# GatewayVote_V2_0.net
KiCad netlist of a schematic drawn in EAGLE
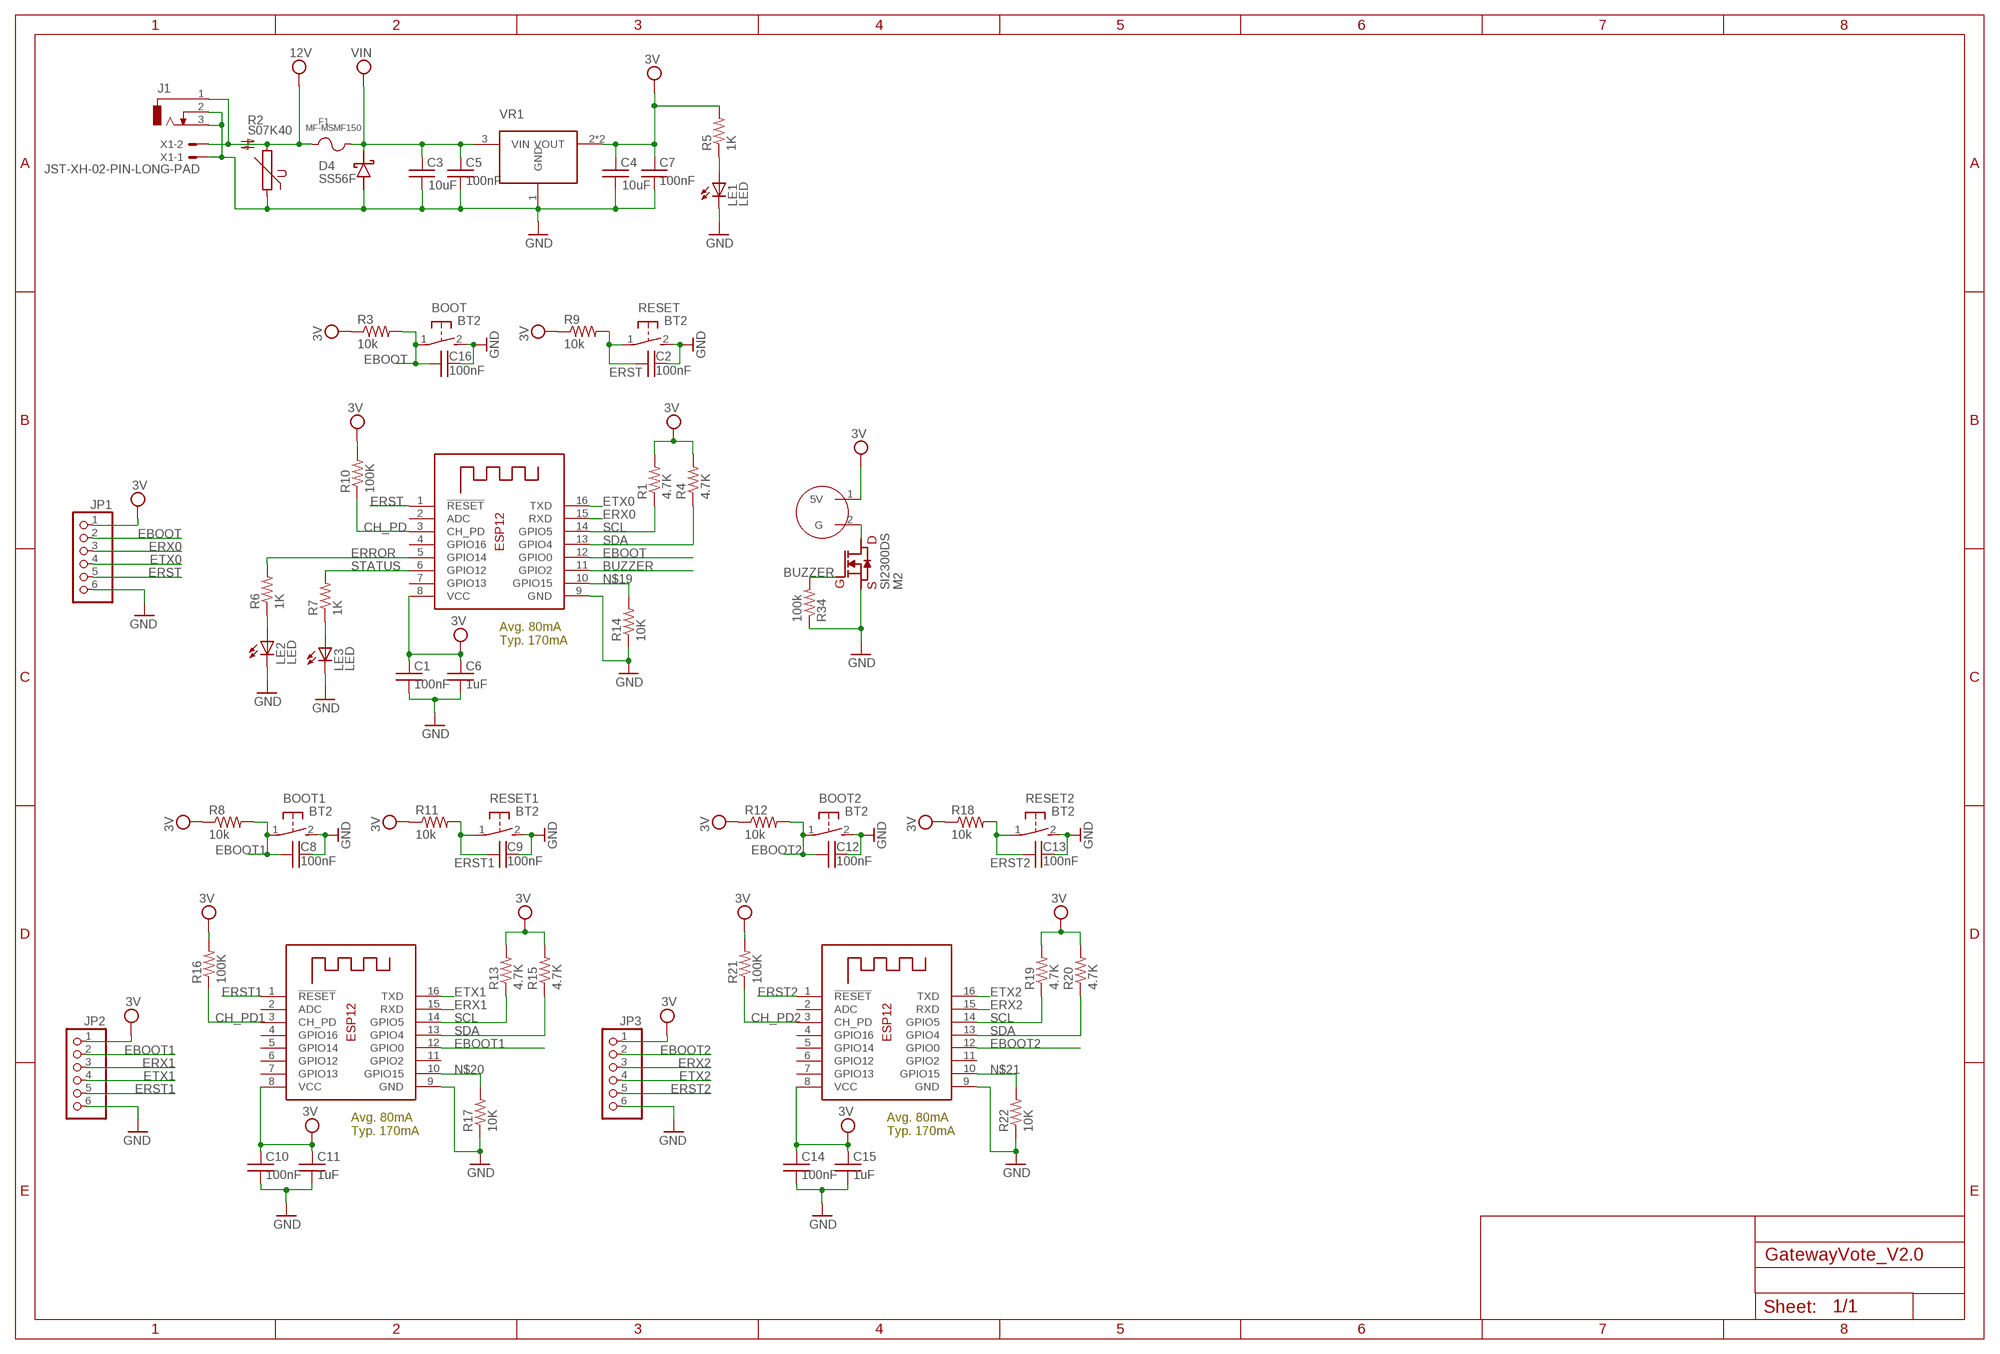
[diagram p0: schematic, sheet 1]

(export (version "E")
  (design (tool "Eeschema 10.0.6"))
  (components
    (comp (ref "BOOT")
      (value "BT2")
      (footprint "eagle-import:BT2")
      (libsource (lib "eagle-import") (part "BT2"))
    )
    (comp (ref "BOOT1")
      (value "BT2")
      (footprint "eagle-import:BT2")
      (libsource (lib "eagle-import") (part "BT2"))
    )
    (comp (ref "BOOT2")
      (value "BT2")
      (footprint "eagle-import:BT2")
      (libsource (lib "eagle-import") (part "BT2"))
    )
    (comp (ref "C1")
      (value "100nF")
      (footprint "eagle-import:0603")
      (libsource (lib "eagle-import") (part "C0603"))
    )
    (comp (ref "C2")
      (value "100nF")
      (footprint "eagle-import:0603")
      (libsource (lib "eagle-import") (part "Dkoi_C0603"))
    )
    (comp (ref "C3")
      (value "10uF")
      (footprint "eagle-import:0603")
      (libsource (lib "eagle-import") (part "Dkoi-updated_C0603"))
    )
    (comp (ref "C4")
      (value "10uF")
      (footprint "eagle-import:0603")
      (libsource (lib "eagle-import") (part "Dkoi-updated_C0603"))
    )
    (comp (ref "C5")
      (value "100nF")
      (footprint "eagle-import:0603")
      (libsource (lib "eagle-import") (part "Dkoi-updated_C0603"))
    )
    (comp (ref "C6")
      (value "1uF")
      (footprint "eagle-import:0603")
      (libsource (lib "eagle-import") (part "C0603"))
    )
    (comp (ref "C7")
      (value "100nF")
      (footprint "eagle-import:0603")
      (libsource (lib "eagle-import") (part "Dkoi-updated_C0603"))
    )
    (comp (ref "C8")
      (value "100nF")
      (footprint "eagle-import:0603")
      (libsource (lib "eagle-import") (part "Dkoi_C0603"))
    )
    (comp (ref "C9")
      (value "100nF")
      (footprint "eagle-import:0603")
      (libsource (lib "eagle-import") (part "Dkoi_C0603"))
    )
    (comp (ref "C10")
      (value "100nF")
      (footprint "eagle-import:0603")
      (libsource (lib "eagle-import") (part "C0603"))
    )
    (comp (ref "C11")
      (value "1uF")
      (footprint "eagle-import:0603")
      (libsource (lib "eagle-import") (part "C0603"))
    )
    (comp (ref "C12")
      (value "100nF")
      (footprint "eagle-import:0603")
      (libsource (lib "eagle-import") (part "Dkoi_C0603"))
    )
    (comp (ref "C13")
      (value "100nF")
      (footprint "eagle-import:0603")
      (libsource (lib "eagle-import") (part "Dkoi_C0603"))
    )
    (comp (ref "C14")
      (value "100nF")
      (footprint "eagle-import:0603")
      (libsource (lib "eagle-import") (part "C0603"))
    )
    (comp (ref "C15")
      (value "1uF")
      (footprint "eagle-import:0603")
      (libsource (lib "eagle-import") (part "C0603"))
    )
    (comp (ref "C16")
      (value "100nF")
      (footprint "eagle-import:0603")
      (libsource (lib "eagle-import") (part "Dkoi_C0603"))
    )
    (comp (ref "D4")
      (value "SS56F")
      (footprint "eagle-import:SMB")
      (libsource (lib "eagle-import") (part "SS56F"))
    )
    (comp (ref "F1")
      (value "MF-MSMF150")
      (footprint "eagle-import:FUSER_MF-MSMF150")
      (fields (field (name "MF") "Bourns"))
      (libsource (lib "eagle-import") (part "MF-MSMF150"))
    )
    (comp (ref "J1")
      (value "DCJ0303")
      (footprint "eagle-import:DCJ0303")
      (libsource (lib "eagle-import") (part "DCJ0303"))
    )
    (comp (ref "JP1")
      (value "PINHD-1X6")
      (footprint "eagle-import:1X06")
      (libsource (lib "eagle-import") (part "PINHD-1X6"))
    )
    (comp (ref "JP2")
      (value "PINHD-1X6")
      (footprint "eagle-import:1X06")
      (libsource (lib "eagle-import") (part "PINHD-1X6"))
    )
    (comp (ref "JP3")
      (value "PINHD-1X6")
      (footprint "eagle-import:1X06")
      (libsource (lib "eagle-import") (part "PINHD-1X6"))
    )
    (comp (ref "LE1")
      (value "LED")
      (footprint "eagle-import:LED3MM")
      (libsource (lib "eagle-import") (part "LED"))
    )
    (comp (ref "LE2")
      (value "LED")
      (footprint "eagle-import:LED3MM")
      (libsource (lib "eagle-import") (part "LED"))
    )
    (comp (ref "LE3")
      (value "LED")
      (footprint "eagle-import:LED3MM")
      (libsource (lib "eagle-import") (part "LED"))
    )
    (comp (ref "M2")
      (value "SI2300DS")
      (footprint "eagle-import:SOT23(1)")
      (libsource (lib "eagle-import") (part "MOSFETN"))
    )
    (comp (ref "R1")
      (value "4.7K")
      (footprint "eagle-import:0603")
      (libsource (lib "eagle-import") (part "Dkoi-updated_31355864_R0603"))
    )
    (comp (ref "R2")
      (value "S07K40")
      (footprint "eagle-import:S07K40")
      (libsource (lib "eagle-import") (part "S07K40"))
    )
    (comp (ref "R3")
      (value "10k")
      (footprint "eagle-import:0603")
      (libsource (lib "eagle-import") (part "R0603"))
    )
    (comp (ref "R4")
      (value "4.7K")
      (footprint "eagle-import:0603")
      (libsource (lib "eagle-import") (part "Dkoi-updated_31355864_R0603"))
    )
    (comp (ref "R5")
      (value "1K")
      (footprint "eagle-import:0603")
      (libsource (lib "eagle-import") (part "Dkoi-updated_31355864_R0603"))
    )
    (comp (ref "R6")
      (value "1K")
      (footprint "eagle-import:0603")
      (libsource (lib "eagle-import") (part "Dkoi-updated_31355864_R0603"))
    )
    (comp (ref "R7")
      (value "1K")
      (footprint "eagle-import:0603")
      (libsource (lib "eagle-import") (part "Dkoi-updated_31355864_R0603"))
    )
    (comp (ref "R8")
      (value "10k")
      (footprint "eagle-import:0603")
      (libsource (lib "eagle-import") (part "R0603"))
    )
    (comp (ref "R9")
      (value "10k")
      (footprint "eagle-import:0603")
      (libsource (lib "eagle-import") (part "R0603"))
    )
    (comp (ref "R10")
      (value "100K")
      (footprint "eagle-import:0603")
      (libsource (lib "eagle-import") (part "Dkoi-updated_31355864_R0603"))
    )
    (comp (ref "R11")
      (value "10k")
      (footprint "eagle-import:0603")
      (libsource (lib "eagle-import") (part "R0603"))
    )
    (comp (ref "R12")
      (value "10k")
      (footprint "eagle-import:0603")
      (libsource (lib "eagle-import") (part "R0603"))
    )
    (comp (ref "R13")
      (value "4.7K")
      (footprint "eagle-import:0603")
      (libsource (lib "eagle-import") (part "Dkoi-updated_31355864_R0603"))
    )
    (comp (ref "R14")
      (value "10K")
      (footprint "eagle-import:0603")
      (libsource (lib "eagle-import") (part "Dkoi-updated_31355864_R0603"))
    )
    (comp (ref "R15")
      (value "4.7K")
      (footprint "eagle-import:0603")
      (libsource (lib "eagle-import") (part "Dkoi-updated_31355864_R0603"))
    )
    (comp (ref "R16")
      (value "100K")
      (footprint "eagle-import:0603")
      (libsource (lib "eagle-import") (part "Dkoi-updated_31355864_R0603"))
    )
    (comp (ref "R17")
      (value "10K")
      (footprint "eagle-import:0603")
      (libsource (lib "eagle-import") (part "Dkoi-updated_31355864_R0603"))
    )
    (comp (ref "R18")
      (value "10k")
      (footprint "eagle-import:0603")
      (libsource (lib "eagle-import") (part "R0603"))
    )
    (comp (ref "R19")
      (value "4.7K")
      (footprint "eagle-import:0603")
      (libsource (lib "eagle-import") (part "Dkoi-updated_31355864_R0603"))
    )
    (comp (ref "R20")
      (value "4.7K")
      (footprint "eagle-import:0603")
      (libsource (lib "eagle-import") (part "Dkoi-updated_31355864_R0603"))
    )
    (comp (ref "R21")
      (value "100K")
      (footprint "eagle-import:0603")
      (libsource (lib "eagle-import") (part "Dkoi-updated_31355864_R0603"))
    )
    (comp (ref "R22")
      (value "10K")
      (footprint "eagle-import:0603")
      (libsource (lib "eagle-import") (part "Dkoi-updated_31355864_R0603"))
    )
    (comp (ref "R34")
      (value "100k")
      (footprint "eagle-import:0603")
      (libsource (lib "eagle-import") (part "R0603"))
    )
    (comp (ref "RESET")
      (value "BT2")
      (footprint "eagle-import:BT2")
      (libsource (lib "eagle-import") (part "BT2"))
    )
    (comp (ref "RESET1")
      (value "BT2")
      (footprint "eagle-import:BT2")
      (libsource (lib "eagle-import") (part "BT2"))
    )
    (comp (ref "RESET2")
      (value "BT2")
      (footprint "eagle-import:BT2")
      (libsource (lib "eagle-import") (part "BT2"))
    )
    (comp (ref "U$3")
      (value "BUZZER-5V")
      (footprint "eagle-import:BUZZER-5V")
      (libsource (lib "eagle-import") (part "BUZZER-5V"))
    )
    (comp (ref "VR1")
      (value "LD1085D2M33R")
      (footprint "eagle-import:VREG_LD1085D2M33R")
      (fields (field (name "MF") "STMicroelectronics"))
      (libsource (lib "eagle-import") (part "LD1085D2M33R"))
    )
    (comp (ref "X1")
      (value "JST-XH-02-PIN-LONG-PAD")
      (footprint "eagle-import:JST-XH-02-PACKAGE-LONG-PAD")
      (libsource (lib "eagle-import") (part "JST-XH-02-PIN-LONG-PAD"))
    )
    (comp (ref "X2")
      (value "ESP-12")
      (footprint "eagle-import:ESP-12")
      (libsource (lib "eagle-import") (part "ESP-12"))
    )
    (comp (ref "X3")
      (value "ESP-12")
      (footprint "eagle-import:ESP-12")
      (libsource (lib "eagle-import") (part "ESP-12"))
    )
    (comp (ref "X4")
      (value "ESP-12")
      (footprint "eagle-import:ESP-12")
      (libsource (lib "eagle-import") (part "ESP-12"))
    )
  )
  (nets
    (net (code "1") (name "/BUZZER") (class "Default")
      (node (ref "M2") (pin "1") (pinfunction "G_1") (pintype "bidirectional"))
      (node (ref "R34") (pin "2") (pinfunction "2_2") (pintype "passive"))
      (node (ref "X2") (pin "11") (pinfunction "GPIO2_11") (pintype "bidirectional"))
    )
    (net (code "2") (name "/CH_PD") (class "Default")
      (node (ref "R10") (pin "1") (pinfunction "1_1") (pintype "passive"))
      (node (ref "X2") (pin "3") (pinfunction "CH_PD_3") (pintype "input"))
    )
    (net (code "3") (name "/CH_PD1") (class "Default")
      (node (ref "R16") (pin "1") (pinfunction "1_1") (pintype "passive"))
      (node (ref "X3") (pin "3") (pinfunction "CH_PD_3") (pintype "input"))
    )
    (net (code "4") (name "/CH_PD2") (class "Default")
      (node (ref "R21") (pin "1") (pinfunction "1_1") (pintype "passive"))
      (node (ref "X4") (pin "3") (pinfunction "CH_PD_3") (pintype "input"))
    )
    (net (code "5") (name "/EBOOT") (class "Default")
      (node (ref "BOOT") (pin "1") (pinfunction "1_1") (pintype "passive"))
      (node (ref "C16") (pin "1") (pinfunction "1_1") (pintype "passive"))
      (node (ref "JP1") (pin "2") (pinfunction "2_2") (pintype "passive"))
      (node (ref "R3") (pin "2") (pinfunction "2_2") (pintype "passive"))
      (node (ref "X2") (pin "12") (pinfunction "GPIO0_12") (pintype "bidirectional"))
    )
    (net (code "6") (name "/EBOOT1") (class "Default")
      (node (ref "BOOT1") (pin "1") (pinfunction "1_1") (pintype "passive"))
      (node (ref "C8") (pin "1") (pinfunction "1_1") (pintype "passive"))
      (node (ref "JP2") (pin "2") (pinfunction "2_2") (pintype "passive"))
      (node (ref "R8") (pin "2") (pinfunction "2_2") (pintype "passive"))
      (node (ref "X3") (pin "12") (pinfunction "GPIO0_12") (pintype "bidirectional"))
    )
    (net (code "7") (name "/EBOOT2") (class "Default")
      (node (ref "BOOT2") (pin "1") (pinfunction "1_1") (pintype "passive"))
      (node (ref "C12") (pin "1") (pinfunction "1_1") (pintype "passive"))
      (node (ref "JP3") (pin "2") (pinfunction "2_2") (pintype "passive"))
      (node (ref "R12") (pin "2") (pinfunction "2_2") (pintype "passive"))
      (node (ref "X4") (pin "12") (pinfunction "GPIO0_12") (pintype "bidirectional"))
    )
    (net (code "8") (name "/ERROR") (class "Default")
      (node (ref "R6") (pin "2") (pinfunction "2_2") (pintype "passive"))
      (node (ref "X2") (pin "5") (pinfunction "GPIO14_5") (pintype "bidirectional"))
    )
    (net (code "9") (name "/ERST") (class "Default")
      (node (ref "C2") (pin "1") (pinfunction "1_1") (pintype "passive"))
      (node (ref "JP1") (pin "5") (pinfunction "5_5") (pintype "passive"))
      (node (ref "R9") (pin "2") (pinfunction "2_2") (pintype "passive"))
      (node (ref "RESET") (pin "1") (pinfunction "1_1") (pintype "passive"))
      (node (ref "X2") (pin "1") (pinfunction "~{RESET}_1") (pintype "input"))
    )
    (net (code "10") (name "/ERST1") (class "Default")
      (node (ref "C9") (pin "1") (pinfunction "1_1") (pintype "passive"))
      (node (ref "JP2") (pin "5") (pinfunction "5_5") (pintype "passive"))
      (node (ref "R11") (pin "2") (pinfunction "2_2") (pintype "passive"))
      (node (ref "RESET1") (pin "1") (pinfunction "1_1") (pintype "passive"))
      (node (ref "X3") (pin "1") (pinfunction "~{RESET}_1") (pintype "input"))
    )
    (net (code "11") (name "/ERST2") (class "Default")
      (node (ref "C13") (pin "1") (pinfunction "1_1") (pintype "passive"))
      (node (ref "JP3") (pin "5") (pinfunction "5_5") (pintype "passive"))
      (node (ref "R18") (pin "2") (pinfunction "2_2") (pintype "passive"))
      (node (ref "RESET2") (pin "1") (pinfunction "1_1") (pintype "passive"))
      (node (ref "X4") (pin "1") (pinfunction "~{RESET}_1") (pintype "input"))
    )
    (net (code "12") (name "/ERX0") (class "Default")
      (node (ref "JP1") (pin "3") (pinfunction "3_3") (pintype "passive"))
      (node (ref "X2") (pin "15") (pinfunction "RXD_15") (pintype "input"))
    )
    (net (code "13") (name "/ERX1") (class "Default")
      (node (ref "JP2") (pin "3") (pinfunction "3_3") (pintype "passive"))
      (node (ref "X3") (pin "15") (pinfunction "RXD_15") (pintype "input"))
    )
    (net (code "14") (name "/ERX2") (class "Default")
      (node (ref "JP3") (pin "3") (pinfunction "3_3") (pintype "passive"))
      (node (ref "X4") (pin "15") (pinfunction "RXD_15") (pintype "input"))
    )
    (net (code "15") (name "/ETX0") (class "Default")
      (node (ref "JP1") (pin "4") (pinfunction "4_4") (pintype "passive"))
      (node (ref "X2") (pin "16") (pinfunction "TXD_16") (pintype "output"))
    )
    (net (code "16") (name "/ETX1") (class "Default")
      (node (ref "JP2") (pin "4") (pinfunction "4_4") (pintype "passive"))
      (node (ref "X3") (pin "16") (pinfunction "TXD_16") (pintype "output"))
    )
    (net (code "17") (name "/ETX2") (class "Default")
      (node (ref "JP3") (pin "4") (pinfunction "4_4") (pintype "passive"))
      (node (ref "X4") (pin "16") (pinfunction "TXD_16") (pintype "output"))
    )
    (net (code "18") (name "/N$19") (class "Default")
      (node (ref "R14") (pin "2") (pinfunction "2_2") (pintype "passive"))
      (node (ref "X2") (pin "10") (pinfunction "GPIO15_10") (pintype "bidirectional"))
    )
    (net (code "19") (name "/N$20") (class "Default")
      (node (ref "R17") (pin "2") (pinfunction "2_2") (pintype "passive"))
      (node (ref "X3") (pin "10") (pinfunction "GPIO15_10") (pintype "bidirectional"))
    )
    (net (code "20") (name "/N$21") (class "Default")
      (node (ref "R22") (pin "2") (pinfunction "2_2") (pintype "passive"))
      (node (ref "X4") (pin "10") (pinfunction "GPIO15_10") (pintype "bidirectional"))
    )
    (net (code "21") (name "/SCL") (class "Default")
      (node (ref "R1") (pin "1") (pinfunction "1_1") (pintype "passive"))
      (node (ref "R13") (pin "1") (pinfunction "1_1") (pintype "passive"))
      (node (ref "R19") (pin "1") (pinfunction "1_1") (pintype "passive"))
      (node (ref "X2") (pin "14") (pinfunction "GPIO5_14") (pintype "bidirectional"))
      (node (ref "X3") (pin "14") (pinfunction "GPIO5_14") (pintype "bidirectional"))
      (node (ref "X4") (pin "14") (pinfunction "GPIO5_14") (pintype "bidirectional"))
    )
    (net (code "22") (name "/SDA") (class "Default")
      (node (ref "R15") (pin "1") (pinfunction "1_1") (pintype "passive"))
      (node (ref "R20") (pin "1") (pinfunction "1_1") (pintype "passive"))
      (node (ref "R4") (pin "1") (pinfunction "1_1") (pintype "passive"))
      (node (ref "X2") (pin "13") (pinfunction "GPIO4_13") (pintype "bidirectional"))
      (node (ref "X3") (pin "13") (pinfunction "GPIO4_13") (pintype "bidirectional"))
      (node (ref "X4") (pin "13") (pinfunction "GPIO4_13") (pintype "bidirectional"))
    )
    (net (code "23") (name "/STATUS") (class "Default")
      (node (ref "R7") (pin "2") (pinfunction "2_2") (pintype "passive"))
      (node (ref "X2") (pin "6") (pinfunction "GPIO12_6") (pintype "bidirectional"))
    )
    (net (code "24") (name "3V") (class "Default")
      (node (ref "C1") (pin "1") (pinfunction "1_1") (pintype "passive"))
      (node (ref "C10") (pin "1") (pinfunction "1_1") (pintype "passive"))
      (node (ref "C11") (pin "1") (pinfunction "1_1") (pintype "passive"))
      (node (ref "C14") (pin "1") (pinfunction "1_1") (pintype "passive"))
      (node (ref "C15") (pin "1") (pinfunction "1_1") (pintype "passive"))
      (node (ref "C4") (pin "1") (pinfunction "1_1") (pintype "passive"))
      (node (ref "C6") (pin "1") (pinfunction "1_1") (pintype "passive"))
      (node (ref "C7") (pin "1") (pinfunction "1_1") (pintype "passive"))
      (node (ref "JP1") (pin "1") (pinfunction "1_1") (pintype "passive"))
      (node (ref "JP2") (pin "1") (pinfunction "1_1") (pintype "passive"))
      (node (ref "JP3") (pin "1") (pinfunction "1_1") (pintype "passive"))
      (node (ref "R1") (pin "2") (pinfunction "2_2") (pintype "passive"))
      (node (ref "R10") (pin "2") (pinfunction "2_2") (pintype "passive"))
      (node (ref "R11") (pin "1") (pinfunction "1_1") (pintype "passive"))
      (node (ref "R12") (pin "1") (pinfunction "1_1") (pintype "passive"))
      (node (ref "R13") (pin "2") (pinfunction "2_2") (pintype "passive"))
      (node (ref "R15") (pin "2") (pinfunction "2_2") (pintype "passive"))
      (node (ref "R16") (pin "2") (pinfunction "2_2") (pintype "passive"))
      (node (ref "R18") (pin "1") (pinfunction "1_1") (pintype "passive"))
      (node (ref "R19") (pin "2") (pinfunction "2_2") (pintype "passive"))
      (node (ref "R20") (pin "2") (pinfunction "2_2") (pintype "passive"))
      (node (ref "R21") (pin "2") (pinfunction "2_2") (pintype "passive"))
      (node (ref "R3") (pin "1") (pinfunction "1_1") (pintype "passive"))
      (node (ref "R4") (pin "2") (pinfunction "2_2") (pintype "passive"))
      (node (ref "R5") (pin "2") (pinfunction "2_2") (pintype "passive"))
      (node (ref "R8") (pin "1") (pinfunction "1_1") (pintype "passive"))
      (node (ref "R9") (pin "1") (pinfunction "1_1") (pintype "passive"))
      (node (ref "U$3") (pin "1") (pinfunction "5V_1") (pintype "bidirectional"))
      (node (ref "VR1") (pin "2") (pinfunction "VOUT_2") (pintype "bidirectional"))
      (node (ref "VR1") (pin "4") (pinfunction "VOUT_4") (pintype "bidirectional"))
      (node (ref "X2") (pin "8") (pinfunction "VCC_8") (pintype "power_in"))
      (node (ref "X3") (pin "8") (pinfunction "VCC_8") (pintype "power_in"))
      (node (ref "X4") (pin "8") (pinfunction "VCC_8") (pintype "power_in"))
    )
    (net (code "25") (name "12V") (class "Default")
      (node (ref "F1") (pin "1") (pinfunction "1_1") (pintype "passive"))
      (node (ref "J1") (pin "1") (pinfunction "1_1") (pintype "passive"))
      (node (ref "R2") (pin "2") (pinfunction "2_2") (pintype "passive"))
      (node (ref "X1") (pin "2") (pinfunction "S_2") (pintype "passive"))
    )
    (net (code "26") (name "GND") (class "Default")
      (node (ref "BOOT") (pin "2") (pinfunction "2_2") (pintype "passive"))
      (node (ref "BOOT1") (pin "2") (pinfunction "2_2") (pintype "passive"))
      (node (ref "BOOT2") (pin "2") (pinfunction "2_2") (pintype "passive"))
      (node (ref "C1") (pin "2") (pinfunction "2_2") (pintype "passive"))
      (node (ref "C10") (pin "2") (pinfunction "2_2") (pintype "passive"))
      (node (ref "C11") (pin "2") (pinfunction "2_2") (pintype "passive"))
      (node (ref "C12") (pin "2") (pinfunction "2_2") (pintype "passive"))
      (node (ref "C13") (pin "2") (pinfunction "2_2") (pintype "passive"))
      (node (ref "C14") (pin "2") (pinfunction "2_2") (pintype "passive"))
      (node (ref "C15") (pin "2") (pinfunction "2_2") (pintype "passive"))
      (node (ref "C16") (pin "2") (pinfunction "2_2") (pintype "passive"))
      (node (ref "C2") (pin "2") (pinfunction "2_2") (pintype "passive"))
      (node (ref "C3") (pin "2") (pinfunction "2_2") (pintype "passive"))
      (node (ref "C4") (pin "2") (pinfunction "2_2") (pintype "passive"))
      (node (ref "C5") (pin "2") (pinfunction "2_2") (pintype "passive"))
      (node (ref "C6") (pin "2") (pinfunction "2_2") (pintype "passive"))
      (node (ref "C7") (pin "2") (pinfunction "2_2") (pintype "passive"))
      (node (ref "C8") (pin "2") (pinfunction "2_2") (pintype "passive"))
      (node (ref "C9") (pin "2") (pinfunction "2_2") (pintype "passive"))
      (node (ref "D4") (pin "A") (pinfunction "A_A") (pintype "bidirectional"))
      (node (ref "J1") (pin "2") (pinfunction "2_2") (pintype "passive"))
      (node (ref "J1") (pin "3") (pinfunction "3_3") (pintype "passive"))
      (node (ref "JP1") (pin "6") (pinfunction "6_6") (pintype "passive"))
      (node (ref "JP2") (pin "6") (pinfunction "6_6") (pintype "passive"))
      (node (ref "JP3") (pin "6") (pinfunction "6_6") (pintype "passive"))
      (node (ref "LE1") (pin "K") (pinfunction "C_K") (pintype "passive"))
      (node (ref "LE2") (pin "K") (pinfunction "C_K") (pintype "passive"))
      (node (ref "LE3") (pin "K") (pinfunction "C_K") (pintype "passive"))
      (node (ref "M2") (pin "2") (pinfunction "S_2") (pintype "bidirectional"))
      (node (ref "R14") (pin "1") (pinfunction "1_1") (pintype "passive"))
      (node (ref "R17") (pin "1") (pinfunction "1_1") (pintype "passive"))
      (node (ref "R2") (pin "1") (pinfunction "1_1") (pintype "passive"))
      (node (ref "R22") (pin "1") (pinfunction "1_1") (pintype "passive"))
      (node (ref "R34") (pin "1") (pinfunction "1_1") (pintype "passive"))
      (node (ref "RESET") (pin "2") (pinfunction "2_2") (pintype "passive"))
      (node (ref "RESET1") (pin "2") (pinfunction "2_2") (pintype "passive"))
      (node (ref "RESET2") (pin "2") (pinfunction "2_2") (pintype "passive"))
      (node (ref "VR1") (pin "1") (pinfunction "GND_1") (pintype "bidirectional"))
      (node (ref "X1") (pin "1") (pinfunction "S_1") (pintype "passive"))
      (node (ref "X2") (pin "9") (pinfunction "GND_9") (pintype "power_in"))
      (node (ref "X3") (pin "9") (pinfunction "GND_9") (pintype "power_in"))
      (node (ref "X4") (pin "9") (pinfunction "GND_9") (pintype "power_in"))
    )
    (net (code "27") (name "Net-(LE1-PadA)") (class "Default")
      (node (ref "LE1") (pin "A") (pinfunction "A_A") (pintype "passive"))
      (node (ref "R5") (pin "1") (pinfunction "1_1") (pintype "passive"))
    )
    (net (code "28") (name "Net-(LE2-PadA)") (class "Default")
      (node (ref "LE2") (pin "A") (pinfunction "A_A") (pintype "passive"))
      (node (ref "R6") (pin "1") (pinfunction "1_1") (pintype "passive"))
    )
    (net (code "29") (name "Net-(LE3-PadA)") (class "Default")
      (node (ref "LE3") (pin "A") (pinfunction "A_A") (pintype "passive"))
      (node (ref "R7") (pin "1") (pinfunction "1_1") (pintype "passive"))
    )
    (net (code "30") (name "Net-(M2-D)") (class "Default")
      (node (ref "M2") (pin "3") (pinfunction "D_3") (pintype "bidirectional"))
      (node (ref "U$3") (pin "2") (pinfunction "G_2") (pintype "bidirectional"))
    )
    (net (code "31") (name "VIN") (class "Default")
      (node (ref "C3") (pin "1") (pinfunction "1_1") (pintype "passive"))
      (node (ref "C5") (pin "1") (pinfunction "1_1") (pintype "passive"))
      (node (ref "D4") (pin "C") (pinfunction "C_C") (pintype "bidirectional"))
      (node (ref "F1") (pin "2") (pinfunction "2_2") (pintype "passive"))
      (node (ref "VR1") (pin "3") (pinfunction "VIN_3") (pintype "bidirectional"))
    )
    (net (code "32") (name "unconnected-(X2-ADC-Pad2)") (class "Default")
      (node (ref "X2") (pin "2") (pinfunction "ADC_2") (pintype "passive"))
    )
    (net (code "33") (name "unconnected-(X2-GPIO13-Pad7)") (class "Default")
      (node (ref "X2") (pin "7") (pinfunction "GPIO13_7") (pintype "bidirectional"))
    )
    (net (code "34") (name "unconnected-(X2-GPIO16-Pad4)") (class "Default")
      (node (ref "X2") (pin "4") (pinfunction "GPIO16_4") (pintype "bidirectional"))
    )
    (net (code "35") (name "unconnected-(X3-ADC-Pad2)") (class "Default")
      (node (ref "X3") (pin "2") (pinfunction "ADC_2") (pintype "passive"))
    )
    (net (code "36") (name "unconnected-(X3-GPIO2-Pad11)") (class "Default")
      (node (ref "X3") (pin "11") (pinfunction "GPIO2_11") (pintype "bidirectional"))
    )
    (net (code "37") (name "unconnected-(X3-GPIO12-Pad6)") (class "Default")
      (node (ref "X3") (pin "6") (pinfunction "GPIO12_6") (pintype "bidirectional"))
    )
    (net (code "38") (name "unconnected-(X3-GPIO13-Pad7)") (class "Default")
      (node (ref "X3") (pin "7") (pinfunction "GPIO13_7") (pintype "bidirectional"))
    )
    (net (code "39") (name "unconnected-(X3-GPIO14-Pad5)") (class "Default")
      (node (ref "X3") (pin "5") (pinfunction "GPIO14_5") (pintype "bidirectional"))
    )
    (net (code "40") (name "unconnected-(X3-GPIO16-Pad4)") (class "Default")
      (node (ref "X3") (pin "4") (pinfunction "GPIO16_4") (pintype "bidirectional"))
    )
    (net (code "41") (name "unconnected-(X4-ADC-Pad2)") (class "Default")
      (node (ref "X4") (pin "2") (pinfunction "ADC_2") (pintype "passive"))
    )
    (net (code "42") (name "unconnected-(X4-GPIO2-Pad11)") (class "Default")
      (node (ref "X4") (pin "11") (pinfunction "GPIO2_11") (pintype "bidirectional"))
    )
    (net (code "43") (name "unconnected-(X4-GPIO12-Pad6)") (class "Default")
      (node (ref "X4") (pin "6") (pinfunction "GPIO12_6") (pintype "bidirectional"))
    )
    (net (code "44") (name "unconnected-(X4-GPIO13-Pad7)") (class "Default")
      (node (ref "X4") (pin "7") (pinfunction "GPIO13_7") (pintype "bidirectional"))
    )
    (net (code "45") (name "unconnected-(X4-GPIO14-Pad5)") (class "Default")
      (node (ref "X4") (pin "5") (pinfunction "GPIO14_5") (pintype "bidirectional"))
    )
    (net (code "46") (name "unconnected-(X4-GPIO16-Pad4)") (class "Default")
      (node (ref "X4") (pin "4") (pinfunction "GPIO16_4") (pintype "bidirectional"))
    )
  )
)
